# LazeMEGA.net
KiCad netlist of a schematic drawn in Altium Designer
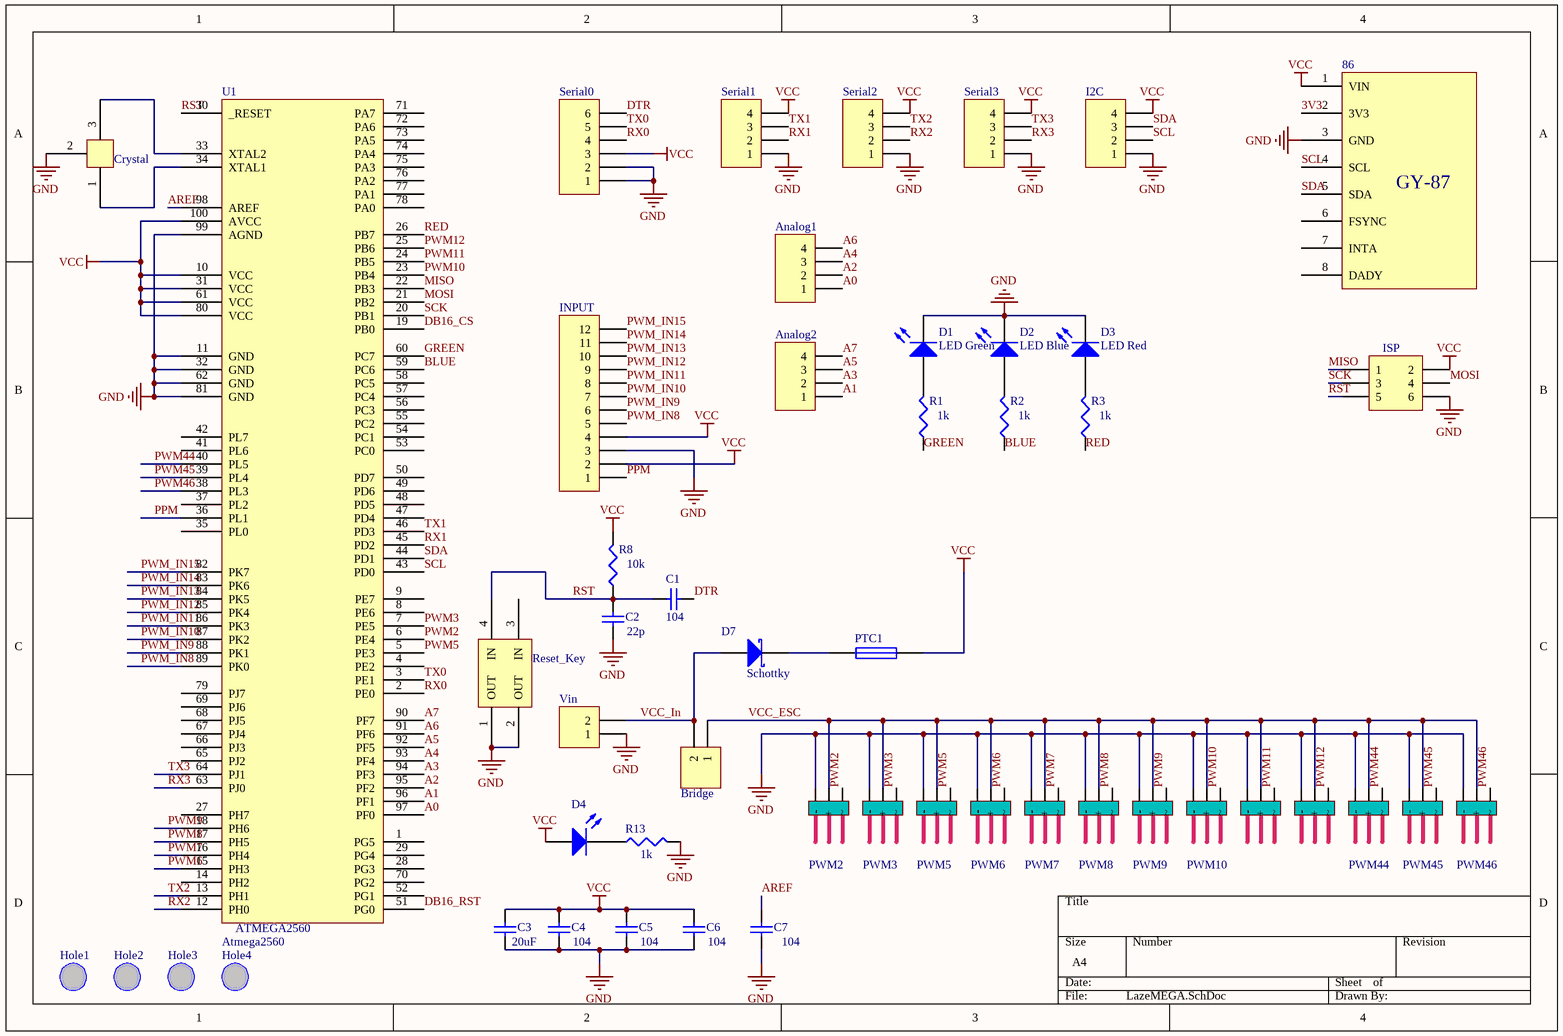
[diagram p0: LazeMEGA.SchDoc]

(export (version "E")
  (design (tool "Eeschema 10.0.6"))
  (components
    (comp (ref "86") (value "~") (footprint "GY-87") (libsource (lib "Drone") (part "GY-87")))
    (comp (ref "Analog1")
      (value "Header 4")
      (footprint "HDR1X4")
      (description "Header, 4-Pin")
      (fields (field (name "PUBLISHER") "Altium Limited"))
      (libsource (lib "Miscellaneous Connectors") (part "Header 4"))
    )
    (comp (ref "Analog2")
      (value "Header 4")
      (footprint "HDR1X4")
      (description "Header, 4-Pin")
      (fields (field (name "PUBLISHER") "Altium Limited"))
      (libsource (lib "Miscellaneous Connectors") (part "Header 4"))
    )
    (comp (ref "Bridge")
      (value "Header 2")
      (footprint "HDR1X2")
      (description "Header, 2-Pin")
      (fields (field (name "PUBLISHER") "Altium Limited"))
      (libsource (lib "Miscellaneous Connectors") (part "Header 2"))
    )
    (comp (ref "C1")
      (value "104")
      (footprint "CAPC1608L")
      (description "Capacitor (Semiconductor SIM Model)")
      (fields (field (name "PUBLISHER") "Altium Limited"))
      (libsource (lib "Miscellaneous Devices") (part "Cap Semi"))
    )
    (comp (ref "C2")
      (value "22p")
      (footprint "CAPC1608L")
      (description "Capacitor (Semiconductor SIM Model)")
      (fields (field (name "PUBLISHER") "Altium Limited"))
      (libsource (lib "Miscellaneous Devices") (part "Cap Semi"))
    )
    (comp (ref "C3")
      (value "20uF")
      (footprint "CAPC3216L")
      (description "Capacitor (Semiconductor SIM Model)")
      (fields (field (name "PUBLISHER") "Altium Limited"))
      (libsource (lib "Miscellaneous Devices") (part "Cap Semi"))
    )
    (comp (ref "C4")
      (value "104")
      (footprint "CAPC1608L")
      (description "Capacitor (Semiconductor SIM Model)")
      (fields (field (name "PUBLISHER") "Altium Limited"))
      (libsource (lib "Miscellaneous Devices") (part "Cap Semi"))
    )
    (comp (ref "C5")
      (value "104")
      (footprint "CAPC1608L")
      (description "Capacitor (Semiconductor SIM Model)")
      (fields (field (name "PUBLISHER") "Altium Limited"))
      (libsource (lib "Miscellaneous Devices") (part "Cap Semi"))
    )
    (comp (ref "C6")
      (value "104")
      (footprint "CAPC1608L")
      (description "Capacitor (Semiconductor SIM Model)")
      (fields (field (name "PUBLISHER") "Altium Limited"))
      (libsource (lib "Miscellaneous Devices") (part "Cap Semi"))
    )
    (comp (ref "C7")
      (value "104")
      (footprint "CAPC1608L")
      (description "Capacitor (Semiconductor SIM Model)")
      (fields (field (name "PUBLISHER") "Altium Limited"))
      (libsource (lib "Miscellaneous Devices") (part "Cap Semi"))
    )
    (comp (ref "Crystal")
      (value "Crystal 16M")
      (footprint "Crystal3Foot")
      (libsource (lib "Drone") (part "Crystal3Foot"))
    )
    (comp (ref "D1")
      (value "LED Green")
      (footprint "CAPC2012L")
      (description "Typical RED, GREEN, YELLOW, AMBER GaAs LED")
      (fields (field (name "PUBLISHER") "Altium Limited"))
      (libsource (lib "Miscellaneous Devices") (part "LED2"))
    )
    (comp (ref "D2")
      (value "LED Blue")
      (footprint "CAPC2012L")
      (description "Typical RED, GREEN, YELLOW, AMBER GaAs LED")
      (fields (field (name "PUBLISHER") "Altium Limited"))
      (libsource (lib "Miscellaneous Devices") (part "LED2"))
    )
    (comp (ref "D3")
      (value "LED Red")
      (footprint "CAPC2012L")
      (description "Typical RED, GREEN, YELLOW, AMBER GaAs LED")
      (fields (field (name "PUBLISHER") "Altium Limited"))
      (libsource (lib "Miscellaneous Devices") (part "LED2"))
    )
    (comp (ref "D4")
      (value "LED Red")
      (footprint "CAPC2012L")
      (description "Typical RED, GREEN, YELLOW, AMBER GaAs LED")
      (fields (field (name "PUBLISHER") "Altium Limited"))
      (libsource (lib "Miscellaneous Devices") (part "LED2"))
    )
    (comp (ref "D7")
      (value "Schottky")
      (footprint "CAPC3216L")
      (description "Schottky Diode")
      (fields (field (name "PUBLISHER") "Altium Limited"))
      (libsource (lib "Miscellaneous Devices") (part "D Schottky"))
    )
    (comp (ref "Hole1")
      (value "3mmHole")
      (footprint "3mmHoleSmall")
      (libsource (lib "Drone") (part "3mmHole"))
    )
    (comp (ref "Hole2")
      (value "3mmHole")
      (footprint "3mmHoleSmall")
      (libsource (lib "Drone") (part "3mmHole"))
    )
    (comp (ref "Hole3")
      (value "3mmHole")
      (footprint "3mmHoleSmall")
      (libsource (lib "Drone") (part "3mmHole"))
    )
    (comp (ref "Hole4")
      (value "3mmHole")
      (footprint "3mmHoleSmall")
      (libsource (lib "Drone") (part "3mmHole"))
    )
    (comp (ref "I2C")
      (value "Header 4")
      (footprint "HDR1X4")
      (description "Header, 4-Pin")
      (fields (field (name "PUBLISHER") "Altium Limited"))
      (libsource (lib "Miscellaneous Connectors") (part "Header 4"))
    )
    (comp (ref "INPUT")
      (value "Header 12")
      (footprint "HDR1X12")
      (description "Header, 12-Pin")
      (fields (field (name "PUBLISHER") "Altium Limited"))
      (libsource (lib "Miscellaneous Connectors") (part "Header 12"))
    )
    (comp (ref "ISP")
      (value "Header 3X2")
      (footprint "HDR2X3")
      (description "Header, 3-Pin, Dual row")
      (fields (field (name "PUBLISHER") "Altium Limited"))
      (libsource (lib "Miscellaneous Connectors") (part "Header 3X2"))
    )
    (comp (ref "JP1")
      (value "Servo out 1")
      (footprint "JP")
      (description "Header, 3-Pin, 0.1\"")
      (fields (field (name "MANUFACTURER") "Generic Components"))
      (libsource (lib "Drone") (part "Hdr 3 Pin 0.1"))
    )
    (comp (ref "JP2")
      (value "Servo out 1")
      (footprint "JP")
      (description "Header, 3-Pin, 0.1\"")
      (fields (field (name "MANUFACTURER") "Generic Components"))
      (libsource (lib "Drone") (part "Hdr 3 Pin 0.1"))
    )
    (comp (ref "PTC1")
      (value "Fuse")
      (footprint "CAPC3216L")
      (fields (field (name "PUBLISHER") "Altium Limited"))
      (libsource (lib "Miscellaneous Devices") (part "Fuse 1"))
    )
    (comp (ref "PWM2")
      (value "Servo out 1")
      (footprint "JP")
      (description "Header, 3-Pin, 0.1\"")
      (fields (field (name "MANUFACTURER") "Generic Components"))
      (libsource (lib "Drone") (part "Hdr 3 Pin 0.1"))
    )
    (comp (ref "PWM3")
      (value "Servo out 1")
      (footprint "JP")
      (description "Header, 3-Pin, 0.1\"")
      (fields (field (name "MANUFACTURER") "Generic Components"))
      (libsource (lib "Drone") (part "Hdr 3 Pin 0.1"))
    )
    (comp (ref "PWM5")
      (value "Servo out 1")
      (footprint "JP")
      (description "Header, 3-Pin, 0.1\"")
      (fields (field (name "MANUFACTURER") "Generic Components"))
      (libsource (lib "Drone") (part "Hdr 3 Pin 0.1"))
    )
    (comp (ref "PWM6")
      (value "Servo out 1")
      (footprint "JP")
      (description "Header, 3-Pin, 0.1\"")
      (fields (field (name "MANUFACTURER") "Generic Components"))
      (libsource (lib "Drone") (part "Hdr 3 Pin 0.1"))
    )
    (comp (ref "PWM7")
      (value "Servo out 1")
      (footprint "JP")
      (description "Header, 3-Pin, 0.1\"")
      (fields (field (name "MANUFACTURER") "Generic Components"))
      (libsource (lib "Drone") (part "Hdr 3 Pin 0.1"))
    )
    (comp (ref "PWM8")
      (value "Servo out 1")
      (footprint "JP")
      (description "Header, 3-Pin, 0.1\"")
      (fields (field (name "MANUFACTURER") "Generic Components"))
      (libsource (lib "Drone") (part "Hdr 3 Pin 0.1"))
    )
    (comp (ref "PWM9")
      (value "Servo out 1")
      (footprint "JP")
      (description "Header, 3-Pin, 0.1\"")
      (fields (field (name "MANUFACTURER") "Generic Components"))
      (libsource (lib "Drone") (part "Hdr 3 Pin 0.1"))
    )
    (comp (ref "PWM10")
      (value "Servo out 1")
      (footprint "JP")
      (description "Header, 3-Pin, 0.1\"")
      (fields (field (name "MANUFACTURER") "Generic Components"))
      (libsource (lib "Drone") (part "Hdr 3 Pin 0.1"))
    )
    (comp (ref "PWM44")
      (value "Servo out 1")
      (footprint "JP")
      (description "Header, 3-Pin, 0.1\"")
      (fields (field (name "MANUFACTURER") "Generic Components"))
      (libsource (lib "Drone") (part "Hdr 3 Pin 0.1"))
    )
    (comp (ref "PWM45")
      (value "Servo out 1")
      (footprint "JP")
      (description "Header, 3-Pin, 0.1\"")
      (fields (field (name "MANUFACTURER") "Generic Components"))
      (libsource (lib "Drone") (part "Hdr 3 Pin 0.1"))
    )
    (comp (ref "PWM46")
      (value "Servo out 1")
      (footprint "JP")
      (description "Header, 3-Pin, 0.1\"")
      (fields (field (name "MANUFACTURER") "Generic Components"))
      (libsource (lib "Drone") (part "Hdr 3 Pin 0.1"))
    )
    (comp (ref "R1")
      (value "1k")
      (footprint "RESC1608L")
      (description "Resistor")
      (fields (field (name "PUBLISHER") "Altium Limited"))
      (libsource (lib "Miscellaneous Devices") (part "Res3"))
    )
    (comp (ref "R2")
      (value "1k")
      (footprint "RESC1608L")
      (description "Resistor")
      (fields (field (name "PUBLISHER") "Altium Limited"))
      (libsource (lib "Miscellaneous Devices") (part "Res3"))
    )
    (comp (ref "R3")
      (value "1k")
      (footprint "RESC1608L")
      (description "Resistor")
      (fields (field (name "PUBLISHER") "Altium Limited"))
      (libsource (lib "Miscellaneous Devices") (part "Res3"))
    )
    (comp (ref "R8")
      (value "10k")
      (footprint "RESC1608L")
      (description "Resistor")
      (fields (field (name "PUBLISHER") "Altium Limited"))
      (libsource (lib "Miscellaneous Devices") (part "Res3"))
    )
    (comp (ref "R13")
      (value "1k")
      (footprint "RESC1608L")
      (description "Resistor")
      (fields (field (name "PUBLISHER") "Altium Limited"))
      (libsource (lib "Miscellaneous Devices") (part "Res3"))
    )
    (comp (ref "Reset_Key") (value "Key") (footprint "Key") (libsource (lib "Drone") (part "Key")))
    (comp (ref "Serial0")
      (value "Header 6")
      (footprint "HDR1X6")
      (description "Header, 6-Pin")
      (fields (field (name "PUBLISHER") "Altium Limited"))
      (libsource (lib "Miscellaneous Connectors") (part "Header 6"))
    )
    (comp (ref "Serial1")
      (value "Header 4")
      (footprint "HDR1X4")
      (description "Header, 4-Pin")
      (fields (field (name "PUBLISHER") "Altium Limited"))
      (libsource (lib "Miscellaneous Connectors") (part "Header 4"))
    )
    (comp (ref "Serial2")
      (value "Header 4")
      (footprint "HDR1X4")
      (description "Header, 4-Pin")
      (fields (field (name "PUBLISHER") "Altium Limited"))
      (libsource (lib "Miscellaneous Connectors") (part "Header 4"))
    )
    (comp (ref "Serial3")
      (value "Header 4")
      (footprint "HDR1X4")
      (description "Header, 4-Pin")
      (fields (field (name "PUBLISHER") "Altium Limited"))
      (libsource (lib "Miscellaneous Connectors") (part "Header 4"))
    )
    (comp (ref "U1")
      (value "Atmega2560")
      (footprint "ATMEGA2560")
      (libsource (lib "Drone") (part "Atmega2560"))
    )
    (comp (ref "Vin")
      (value "Header 2")
      (footprint "HDR1X2")
      (description "Header, 2-Pin")
      (fields (field (name "PUBLISHER") "Altium Limited"))
      (libsource (lib "") (part "Header 2_1"))
    )
  )
  (nets
    (net (code "1") (name "/3V3") (class "Default")
      (node (ref "86") (pin "2") (pinfunction "3V3_2") (pintype "passive"))
    )
    (net (code "2") (name "/A0") (class "Default")
      (node (ref "Analog1") (pin "1") (pinfunction "1_1") (pintype "passive"))
      (node (ref "U1") (pin "97") (pinfunction "PF0_97") (pintype "passive"))
    )
    (net (code "3") (name "/A1") (class "Default")
      (node (ref "Analog2") (pin "1") (pinfunction "1_1") (pintype "passive"))
      (node (ref "U1") (pin "96") (pinfunction "PF1_96") (pintype "passive"))
    )
    (net (code "4") (name "/A2") (class "Default")
      (node (ref "Analog1") (pin "2") (pinfunction "2_2") (pintype "passive"))
      (node (ref "U1") (pin "95") (pinfunction "PF2_95") (pintype "passive"))
    )
    (net (code "5") (name "/A3") (class "Default")
      (node (ref "Analog2") (pin "2") (pinfunction "2_2") (pintype "passive"))
      (node (ref "U1") (pin "94") (pinfunction "PF3_94") (pintype "passive"))
    )
    (net (code "6") (name "/A4") (class "Default")
      (node (ref "Analog1") (pin "3") (pinfunction "3_3") (pintype "passive"))
      (node (ref "U1") (pin "93") (pinfunction "PF4_93") (pintype "passive"))
    )
    (net (code "7") (name "/A5") (class "Default")
      (node (ref "Analog2") (pin "3") (pinfunction "3_3") (pintype "passive"))
      (node (ref "U1") (pin "92") (pinfunction "PF5_92") (pintype "passive"))
    )
    (net (code "8") (name "/A6") (class "Default")
      (node (ref "Analog1") (pin "4") (pinfunction "4_4") (pintype "passive"))
      (node (ref "U1") (pin "91") (pinfunction "PF6_91") (pintype "passive"))
    )
    (net (code "9") (name "/A7") (class "Default")
      (node (ref "Analog2") (pin "4") (pinfunction "4_4") (pintype "passive"))
      (node (ref "U1") (pin "90") (pinfunction "PF7_90") (pintype "passive"))
    )
    (net (code "10") (name "/AREF") (class "Default")
      (node (ref "C7") (pin "2") (pinfunction "2_2") (pintype "passive"))
      (node (ref "U1") (pin "98") (pinfunction "AREF_98") (pintype "passive"))
    )
    (net (code "11") (name "/BLUE") (class "Default")
      (node (ref "R2") (pin "1") (pinfunction "1_1") (pintype "passive"))
      (node (ref "U1") (pin "59") (pinfunction "PC6_59") (pintype "passive"))
    )
    (net (code "12") (name "/DB16_CS") (class "Default")
      (node (ref "U1") (pin "19") (pinfunction "PB0_19") (pintype "passive"))
    )
    (net (code "13") (name "/DB16_RST") (class "Default")
      (node (ref "U1") (pin "51") (pinfunction "PG0_51") (pintype "passive"))
    )
    (net (code "14") (name "/DTR") (class "Default")
      (node (ref "C1") (pin "2") (pinfunction "2_2") (pintype "passive"))
      (node (ref "Serial0") (pin "6") (pinfunction "6_6") (pintype "passive"))
    )
    (net (code "15") (name "/GREEN") (class "Default")
      (node (ref "R1") (pin "1") (pinfunction "1_1") (pintype "passive"))
      (node (ref "U1") (pin "60") (pinfunction "PC7_60") (pintype "passive"))
    )
    (net (code "16") (name "/MISO") (class "Default")
      (node (ref "ISP") (pin "1") (pinfunction "1_1") (pintype "passive"))
      (node (ref "U1") (pin "22") (pinfunction "PB3_22") (pintype "passive"))
    )
    (net (code "17") (name "/MOSI") (class "Default")
      (node (ref "ISP") (pin "4") (pinfunction "4_4") (pintype "passive"))
      (node (ref "U1") (pin "21") (pinfunction "PB2_21") (pintype "passive"))
    )
    (net (code "18") (name "/PPM") (class "Default")
      (node (ref "INPUT") (pin "1") (pinfunction "1_1") (pintype "passive"))
      (node (ref "U1") (pin "36") (pinfunction "PL1_36") (pintype "passive"))
    )
    (net (code "19") (name "/PWM2") (class "Default")
      (node (ref "PWM2") (pin "1") (pinfunction "~_1") (pintype "passive"))
      (node (ref "U1") (pin "6") (pinfunction "PE4_6") (pintype "passive"))
    )
    (net (code "20") (name "/PWM3") (class "Default")
      (node (ref "PWM3") (pin "1") (pinfunction "~_1") (pintype "passive"))
      (node (ref "U1") (pin "7") (pinfunction "PE5_7") (pintype "passive"))
    )
    (net (code "21") (name "/PWM5") (class "Default")
      (node (ref "PWM5") (pin "1") (pinfunction "~_1") (pintype "passive"))
      (node (ref "U1") (pin "5") (pinfunction "PE3_5") (pintype "passive"))
    )
    (net (code "22") (name "/PWM6") (class "Default")
      (node (ref "PWM6") (pin "1") (pinfunction "~_1") (pintype "passive"))
      (node (ref "U1") (pin "15") (pinfunction "PH3_15") (pintype "passive"))
    )
    (net (code "23") (name "/PWM7") (class "Default")
      (node (ref "PWM7") (pin "1") (pinfunction "~_1") (pintype "passive"))
      (node (ref "U1") (pin "16") (pinfunction "PH4_16") (pintype "passive"))
    )
    (net (code "24") (name "/PWM8") (class "Default")
      (node (ref "PWM8") (pin "1") (pinfunction "~_1") (pintype "passive"))
      (node (ref "U1") (pin "17") (pinfunction "PH5_17") (pintype "passive"))
    )
    (net (code "25") (name "/PWM9") (class "Default")
      (node (ref "PWM9") (pin "1") (pinfunction "~_1") (pintype "passive"))
      (node (ref "U1") (pin "18") (pinfunction "PH6_18") (pintype "passive"))
    )
    (net (code "26") (name "/PWM10") (class "Default")
      (node (ref "PWM10") (pin "1") (pinfunction "~_1") (pintype "passive"))
      (node (ref "U1") (pin "23") (pinfunction "PB4_23") (pintype "passive"))
    )
    (net (code "27") (name "/PWM11") (class "Default")
      (node (ref "JP1") (pin "1") (pinfunction "~_1") (pintype "passive"))
      (node (ref "U1") (pin "24") (pinfunction "PB5_24") (pintype "passive"))
    )
    (net (code "28") (name "/PWM12") (class "Default")
      (node (ref "JP2") (pin "1") (pinfunction "~_1") (pintype "passive"))
      (node (ref "U1") (pin "25") (pinfunction "PB6_25") (pintype "passive"))
    )
    (net (code "29") (name "/PWM44") (class "Default")
      (node (ref "PWM44") (pin "1") (pinfunction "~_1") (pintype "passive"))
      (node (ref "U1") (pin "40") (pinfunction "PL5_40") (pintype "passive"))
    )
    (net (code "30") (name "/PWM45") (class "Default")
      (node (ref "PWM45") (pin "1") (pinfunction "~_1") (pintype "passive"))
      (node (ref "U1") (pin "39") (pinfunction "PL4_39") (pintype "passive"))
    )
    (net (code "31") (name "/PWM46") (class "Default")
      (node (ref "PWM46") (pin "1") (pinfunction "~_1") (pintype "passive"))
      (node (ref "U1") (pin "38") (pinfunction "PL3_38") (pintype "passive"))
    )
    (net (code "32") (name "/PWM_IN8") (class "Default")
      (node (ref "INPUT") (pin "5") (pinfunction "5_5") (pintype "passive"))
      (node (ref "U1") (pin "89") (pinfunction "PK0_89") (pintype "passive"))
    )
    (net (code "33") (name "/PWM_IN9") (class "Default")
      (node (ref "INPUT") (pin "6") (pinfunction "6_6") (pintype "passive"))
      (node (ref "U1") (pin "88") (pinfunction "PK1_88") (pintype "passive"))
    )
    (net (code "34") (name "/PWM_IN10") (class "Default")
      (node (ref "INPUT") (pin "7") (pinfunction "7_7") (pintype "passive"))
      (node (ref "U1") (pin "87") (pinfunction "PK2_87") (pintype "passive"))
    )
    (net (code "35") (name "/PWM_IN11") (class "Default")
      (node (ref "INPUT") (pin "8") (pinfunction "8_8") (pintype "passive"))
      (node (ref "U1") (pin "86") (pinfunction "PK3_86") (pintype "passive"))
    )
    (net (code "36") (name "/PWM_IN12") (class "Default")
      (node (ref "INPUT") (pin "9") (pinfunction "9_9") (pintype "passive"))
      (node (ref "U1") (pin "85") (pinfunction "PK4_85") (pintype "passive"))
    )
    (net (code "37") (name "/PWM_IN13") (class "Default")
      (node (ref "INPUT") (pin "10") (pinfunction "10_10") (pintype "passive"))
      (node (ref "U1") (pin "84") (pinfunction "PK5_84") (pintype "passive"))
    )
    (net (code "38") (name "/PWM_IN14") (class "Default")
      (node (ref "INPUT") (pin "11") (pinfunction "11_11") (pintype "passive"))
      (node (ref "U1") (pin "83") (pinfunction "PK6_83") (pintype "passive"))
    )
    (net (code "39") (name "/PWM_IN15") (class "Default")
      (node (ref "INPUT") (pin "12") (pinfunction "12_12") (pintype "passive"))
      (node (ref "U1") (pin "82") (pinfunction "PK7_82") (pintype "passive"))
    )
    (net (code "40") (name "/RED") (class "Default")
      (node (ref "R3") (pin "1") (pinfunction "1_1") (pintype "passive"))
      (node (ref "U1") (pin "26") (pinfunction "PB7_26") (pintype "passive"))
    )
    (net (code "41") (name "/RST") (class "Default")
      (node (ref "C1") (pin "1") (pinfunction "1_1") (pintype "passive"))
      (node (ref "C2") (pin "1") (pinfunction "1_1") (pintype "passive"))
      (node (ref "ISP") (pin "5") (pinfunction "5_5") (pintype "passive"))
      (node (ref "R8") (pin "1") (pinfunction "1_1") (pintype "passive"))
      (node (ref "Reset_Key") (pin "4") (pinfunction "IN_4") (pintype "passive"))
      (node (ref "U1") (pin "30") (pinfunction "_RESET_30") (pintype "passive"))
    )
    (net (code "42") (name "/RX0") (class "Default")
      (node (ref "Serial0") (pin "4") (pinfunction "4_4") (pintype "passive"))
      (node (ref "U1") (pin "2") (pinfunction "PE0_2") (pintype "passive"))
    )
    (net (code "43") (name "/RX1") (class "Default")
      (node (ref "Serial1") (pin "2") (pinfunction "2_2") (pintype "passive"))
      (node (ref "U1") (pin "45") (pinfunction "PD2_45") (pintype "passive"))
    )
    (net (code "44") (name "/RX2") (class "Default")
      (node (ref "Serial2") (pin "2") (pinfunction "2_2") (pintype "passive"))
      (node (ref "U1") (pin "12") (pinfunction "PH0_12") (pintype "passive"))
    )
    (net (code "45") (name "/RX3") (class "Default")
      (node (ref "Serial3") (pin "2") (pinfunction "2_2") (pintype "passive"))
      (node (ref "U1") (pin "63") (pinfunction "PJ0_63") (pintype "passive"))
    )
    (net (code "46") (name "/SCK") (class "Default")
      (node (ref "ISP") (pin "3") (pinfunction "3_3") (pintype "passive"))
      (node (ref "U1") (pin "20") (pinfunction "PB1_20") (pintype "passive"))
    )
    (net (code "47") (name "/SCL") (class "Default")
      (node (ref "86") (pin "4") (pinfunction "SCL_4") (pintype "passive"))
      (node (ref "I2C") (pin "2") (pinfunction "2_2") (pintype "passive"))
      (node (ref "U1") (pin "43") (pinfunction "PD0_43") (pintype "passive"))
    )
    (net (code "48") (name "/SDA") (class "Default")
      (node (ref "86") (pin "5") (pinfunction "SDA_5") (pintype "passive"))
      (node (ref "I2C") (pin "3") (pinfunction "3_3") (pintype "passive"))
      (node (ref "U1") (pin "44") (pinfunction "PD1_44") (pintype "passive"))
    )
    (net (code "49") (name "/TX0") (class "Default")
      (node (ref "Serial0") (pin "5") (pinfunction "5_5") (pintype "passive"))
      (node (ref "U1") (pin "3") (pinfunction "PE1_3") (pintype "passive"))
    )
    (net (code "50") (name "/TX1") (class "Default")
      (node (ref "Serial1") (pin "3") (pinfunction "3_3") (pintype "passive"))
      (node (ref "U1") (pin "46") (pinfunction "PD3_46") (pintype "passive"))
    )
    (net (code "51") (name "/TX2") (class "Default")
      (node (ref "Serial2") (pin "3") (pinfunction "3_3") (pintype "passive"))
      (node (ref "U1") (pin "13") (pinfunction "PH1_13") (pintype "passive"))
    )
    (net (code "52") (name "/TX3") (class "Default")
      (node (ref "Serial3") (pin "3") (pinfunction "3_3") (pintype "passive"))
      (node (ref "U1") (pin "64") (pinfunction "PJ1_64") (pintype "passive"))
    )
    (net (code "53") (name "/VCC_ESC") (class "Default")
      (node (ref "Bridge") (pin "1") (pinfunction "1_1") (pintype "passive"))
      (node (ref "JP1") (pin "2") (pinfunction "+_2") (pintype "passive"))
      (node (ref "JP2") (pin "2") (pinfunction "+_2") (pintype "passive"))
      (node (ref "PWM10") (pin "2") (pinfunction "+_2") (pintype "passive"))
      (node (ref "PWM2") (pin "2") (pinfunction "+_2") (pintype "passive"))
      (node (ref "PWM3") (pin "2") (pinfunction "+_2") (pintype "passive"))
      (node (ref "PWM44") (pin "2") (pinfunction "+_2") (pintype "passive"))
      (node (ref "PWM45") (pin "2") (pinfunction "+_2") (pintype "passive"))
      (node (ref "PWM46") (pin "2") (pinfunction "+_2") (pintype "passive"))
      (node (ref "PWM5") (pin "2") (pinfunction "+_2") (pintype "passive"))
      (node (ref "PWM6") (pin "2") (pinfunction "+_2") (pintype "passive"))
      (node (ref "PWM7") (pin "2") (pinfunction "+_2") (pintype "passive"))
      (node (ref "PWM8") (pin "2") (pinfunction "+_2") (pintype "passive"))
      (node (ref "PWM9") (pin "2") (pinfunction "+_2") (pintype "passive"))
    )
    (net (code "54") (name "/VCC_In") (class "Default")
      (node (ref "Bridge") (pin "2") (pinfunction "2_2") (pintype "passive"))
      (node (ref "D7") (pin "1") (pinfunction "A_1") (pintype "passive"))
      (node (ref "Vin") (pin "2") (pinfunction "2_2") (pintype "passive"))
    )
    (net (code "55") (name "GND") (class "Default")
      (node (ref "86") (pin "3") (pinfunction "GND_3") (pintype "passive"))
      (node (ref "C2") (pin "2") (pinfunction "2_2") (pintype "passive"))
      (node (ref "C3") (pin "1") (pinfunction "1_1") (pintype "passive"))
      (node (ref "C4") (pin "1") (pinfunction "1_1") (pintype "passive"))
      (node (ref "C5") (pin "1") (pinfunction "1_1") (pintype "passive"))
      (node (ref "C6") (pin "1") (pinfunction "1_1") (pintype "passive"))
      (node (ref "C7") (pin "1") (pinfunction "1_1") (pintype "passive"))
      (node (ref "Crystal") (pin "2") (pinfunction "2_2") (pintype "passive"))
      (node (ref "D1") (pin "2") (pinfunction "K_2") (pintype "passive"))
      (node (ref "D2") (pin "2") (pinfunction "K_2") (pintype "passive"))
      (node (ref "D3") (pin "2") (pinfunction "K_2") (pintype "passive"))
      (node (ref "I2C") (pin "1") (pinfunction "1_1") (pintype "passive"))
      (node (ref "INPUT") (pin "3") (pinfunction "3_3") (pintype "passive"))
      (node (ref "ISP") (pin "6") (pinfunction "6_6") (pintype "passive"))
      (node (ref "JP1") (pin "3") (pinfunction "-_3") (pintype "passive"))
      (node (ref "JP2") (pin "3") (pinfunction "-_3") (pintype "passive"))
      (node (ref "PWM10") (pin "3") (pinfunction "-_3") (pintype "passive"))
      (node (ref "PWM2") (pin "3") (pinfunction "-_3") (pintype "passive"))
      (node (ref "PWM3") (pin "3") (pinfunction "-_3") (pintype "passive"))
      (node (ref "PWM44") (pin "3") (pinfunction "-_3") (pintype "passive"))
      (node (ref "PWM45") (pin "3") (pinfunction "-_3") (pintype "passive"))
      (node (ref "PWM46") (pin "3") (pinfunction "-_3") (pintype "passive"))
      (node (ref "PWM5") (pin "3") (pinfunction "-_3") (pintype "passive"))
      (node (ref "PWM6") (pin "3") (pinfunction "-_3") (pintype "passive"))
      (node (ref "PWM7") (pin "3") (pinfunction "-_3") (pintype "passive"))
      (node (ref "PWM8") (pin "3") (pinfunction "-_3") (pintype "passive"))
      (node (ref "PWM9") (pin "3") (pinfunction "-_3") (pintype "passive"))
      (node (ref "R13") (pin "2") (pinfunction "2_2") (pintype "passive"))
      (node (ref "Reset_Key") (pin "1") (pinfunction "OUT_1") (pintype "passive"))
      (node (ref "Reset_Key") (pin "2") (pinfunction "OUT_2") (pintype "passive"))
      (node (ref "Serial0") (pin "1") (pinfunction "1_1") (pintype "passive"))
      (node (ref "Serial0") (pin "2") (pinfunction "2_2") (pintype "passive"))
      (node (ref "Serial1") (pin "1") (pinfunction "1_1") (pintype "passive"))
      (node (ref "Serial2") (pin "1") (pinfunction "1_1") (pintype "passive"))
      (node (ref "Serial3") (pin "1") (pinfunction "1_1") (pintype "passive"))
      (node (ref "U1") (pin "11") (pinfunction "GND_11") (pintype "passive"))
      (node (ref "U1") (pin "32") (pinfunction "GND_32") (pintype "passive"))
      (node (ref "U1") (pin "62") (pinfunction "GND_62") (pintype "passive"))
      (node (ref "U1") (pin "81") (pinfunction "GND_81") (pintype "passive"))
      (node (ref "U1") (pin "99") (pinfunction "AGND_99") (pintype "passive"))
      (node (ref "Vin") (pin "1") (pinfunction "1_1") (pintype "passive"))
    )
    (net (code "56") (name "Net-(Crystal-0)") (class "Default")
      (node (ref "Crystal") (pin "1") (pinfunction "0_1") (pintype "passive"))
      (node (ref "U1") (pin "34") (pinfunction "XTAL1_34") (pintype "passive"))
    )
    (net (code "57") (name "Net-(Crystal-1)") (class "Default")
      (node (ref "Crystal") (pin "3") (pinfunction "1_3") (pintype "passive"))
      (node (ref "U1") (pin "33") (pinfunction "XTAL2_33") (pintype "passive"))
    )
    (net (code "58") (name "Net-(D1-A)") (class "Default")
      (node (ref "D1") (pin "1") (pinfunction "A_1") (pintype "passive"))
      (node (ref "R1") (pin "2") (pinfunction "2_2") (pintype "passive"))
    )
    (net (code "59") (name "Net-(D2-A)") (class "Default")
      (node (ref "D2") (pin "1") (pinfunction "A_1") (pintype "passive"))
      (node (ref "R2") (pin "2") (pinfunction "2_2") (pintype "passive"))
    )
    (net (code "60") (name "Net-(D3-A)") (class "Default")
      (node (ref "D3") (pin "1") (pinfunction "A_1") (pintype "passive"))
      (node (ref "R3") (pin "2") (pinfunction "2_2") (pintype "passive"))
    )
    (net (code "61") (name "Net-(D4-K)") (class "Default")
      (node (ref "D4") (pin "2") (pinfunction "K_2") (pintype "passive"))
      (node (ref "R13") (pin "1") (pinfunction "1_1") (pintype "passive"))
    )
    (net (code "62") (name "Net-(D7-K)") (class "Default")
      (node (ref "D7") (pin "2") (pinfunction "K_2") (pintype "passive"))
      (node (ref "PTC1") (pin "1") (pinfunction "1_1") (pintype "passive"))
    )
    (net (code "63") (name "VCC") (class "Default")
      (node (ref "86") (pin "1") (pinfunction "VIN_1") (pintype "passive"))
      (node (ref "C3") (pin "2") (pinfunction "2_2") (pintype "passive"))
      (node (ref "C4") (pin "2") (pinfunction "2_2") (pintype "passive"))
      (node (ref "C5") (pin "2") (pinfunction "2_2") (pintype "passive"))
      (node (ref "C6") (pin "2") (pinfunction "2_2") (pintype "passive"))
      (node (ref "D4") (pin "1") (pinfunction "A_1") (pintype "passive"))
      (node (ref "I2C") (pin "4") (pinfunction "4_4") (pintype "passive"))
      (node (ref "INPUT") (pin "2") (pinfunction "2_2") (pintype "passive"))
      (node (ref "INPUT") (pin "4") (pinfunction "4_4") (pintype "passive"))
      (node (ref "ISP") (pin "2") (pinfunction "2_2") (pintype "passive"))
      (node (ref "PTC1") (pin "2") (pinfunction "2_2") (pintype "passive"))
      (node (ref "R8") (pin "2") (pinfunction "2_2") (pintype "passive"))
      (node (ref "Serial0") (pin "3") (pinfunction "3_3") (pintype "passive"))
      (node (ref "Serial1") (pin "4") (pinfunction "4_4") (pintype "passive"))
      (node (ref "Serial2") (pin "4") (pinfunction "4_4") (pintype "passive"))
      (node (ref "Serial3") (pin "4") (pinfunction "4_4") (pintype "passive"))
      (node (ref "U1") (pin "10") (pinfunction "VCC_10") (pintype "passive"))
      (node (ref "U1") (pin "100") (pinfunction "AVCC_100") (pintype "passive"))
      (node (ref "U1") (pin "31") (pinfunction "VCC_31") (pintype "passive"))
      (node (ref "U1") (pin "61") (pinfunction "VCC_61") (pintype "passive"))
      (node (ref "U1") (pin "80") (pinfunction "VCC_80") (pintype "passive"))
    )
    (net (code "64") (name "unconnected-(86-DADY-Pad8)") (class "Default")
      (node (ref "86") (pin "8") (pinfunction "DADY_8") (pintype "passive"))
    )
    (net (code "65") (name "unconnected-(86-FSYNC-Pad6)") (class "Default")
      (node (ref "86") (pin "6") (pinfunction "FSYNC_6") (pintype "passive"))
    )
    (net (code "66") (name "unconnected-(86-INTA-Pad7)") (class "Default")
      (node (ref "86") (pin "7") (pinfunction "INTA_7") (pintype "passive"))
    )
    (net (code "67") (name "unconnected-(Reset_Key-IN-Pad3)") (class "Default")
      (node (ref "Reset_Key") (pin "3") (pinfunction "IN_3") (pintype "passive"))
    )
    (net (code "68") (name "unconnected-(U1-PA0-Pad78)") (class "Default")
      (node (ref "U1") (pin "78") (pinfunction "PA0_78") (pintype "passive"))
    )
    (net (code "69") (name "unconnected-(U1-PA1-Pad77)") (class "Default")
      (node (ref "U1") (pin "77") (pinfunction "PA1_77") (pintype "passive"))
    )
    (net (code "70") (name "unconnected-(U1-PA2-Pad76)") (class "Default")
      (node (ref "U1") (pin "76") (pinfunction "PA2_76") (pintype "passive"))
    )
    (net (code "71") (name "unconnected-(U1-PA3-Pad75)") (class "Default")
      (node (ref "U1") (pin "75") (pinfunction "PA3_75") (pintype "passive"))
    )
    (net (code "72") (name "unconnected-(U1-PA4-Pad74)") (class "Default")
      (node (ref "U1") (pin "74") (pinfunction "PA4_74") (pintype "passive"))
    )
    (net (code "73") (name "unconnected-(U1-PA5-Pad73)") (class "Default")
      (node (ref "U1") (pin "73") (pinfunction "PA5_73") (pintype "passive"))
    )
    (net (code "74") (name "unconnected-(U1-PA6-Pad72)") (class "Default")
      (node (ref "U1") (pin "72") (pinfunction "PA6_72") (pintype "passive"))
    )
    (net (code "75") (name "unconnected-(U1-PA7-Pad71)") (class "Default")
      (node (ref "U1") (pin "71") (pinfunction "PA7_71") (pintype "passive"))
    )
    (net (code "76") (name "unconnected-(U1-PC0-Pad53)") (class "Default")
      (node (ref "U1") (pin "53") (pinfunction "PC0_53") (pintype "passive"))
    )
    (net (code "77") (name "unconnected-(U1-PC1-Pad54)") (class "Default")
      (node (ref "U1") (pin "54") (pinfunction "PC1_54") (pintype "passive"))
    )
    (net (code "78") (name "unconnected-(U1-PC2-Pad55)") (class "Default")
      (node (ref "U1") (pin "55") (pinfunction "PC2_55") (pintype "passive"))
    )
    (net (code "79") (name "unconnected-(U1-PC3-Pad56)") (class "Default")
      (node (ref "U1") (pin "56") (pinfunction "PC3_56") (pintype "passive"))
    )
    (net (code "80") (name "unconnected-(U1-PC4-Pad57)") (class "Default")
      (node (ref "U1") (pin "57") (pinfunction "PC4_57") (pintype "passive"))
    )
    (net (code "81") (name "unconnected-(U1-PC5-Pad58)") (class "Default")
      (node (ref "U1") (pin "58") (pinfunction "PC5_58") (pintype "passive"))
    )
    (net (code "82") (name "unconnected-(U1-PD4-Pad47)") (class "Default")
      (node (ref "U1") (pin "47") (pinfunction "PD4_47") (pintype "passive"))
    )
    (net (code "83") (name "unconnected-(U1-PD5-Pad48)") (class "Default")
      (node (ref "U1") (pin "48") (pinfunction "PD5_48") (pintype "passive"))
    )
    (net (code "84") (name "unconnected-(U1-PD6-Pad49)") (class "Default")
      (node (ref "U1") (pin "49") (pinfunction "PD6_49") (pintype "passive"))
    )
    (net (code "85") (name "unconnected-(U1-PD7-Pad50)") (class "Default")
      (node (ref "U1") (pin "50") (pinfunction "PD7_50") (pintype "passive"))
    )
    (net (code "86") (name "unconnected-(U1-PE2-Pad4)") (class "Default")
      (node (ref "U1") (pin "4") (pinfunction "PE2_4") (pintype "passive"))
    )
    (net (code "87") (name "unconnected-(U1-PE6-Pad8)") (class "Default")
      (node (ref "U1") (pin "8") (pinfunction "PE6_8") (pintype "passive"))
    )
    (net (code "88") (name "unconnected-(U1-PE7-Pad9)") (class "Default")
      (node (ref "U1") (pin "9") (pinfunction "PE7_9") (pintype "passive"))
    )
    (net (code "89") (name "unconnected-(U1-PG1-Pad52)") (class "Default")
      (node (ref "U1") (pin "52") (pinfunction "PG1_52") (pintype "passive"))
    )
    (net (code "90") (name "unconnected-(U1-PG2-Pad70)") (class "Default")
      (node (ref "U1") (pin "70") (pinfunction "PG2_70") (pintype "passive"))
    )
    (net (code "91") (name "unconnected-(U1-PG3-Pad28)") (class "Default")
      (node (ref "U1") (pin "28") (pinfunction "PG3_28") (pintype "passive"))
    )
    (net (code "92") (name "unconnected-(U1-PG4-Pad29)") (class "Default")
      (node (ref "U1") (pin "29") (pinfunction "PG4_29") (pintype "passive"))
    )
    (net (code "93") (name "unconnected-(U1-PG5-Pad1)") (class "Default")
      (node (ref "U1") (pin "1") (pinfunction "PG5_1") (pintype "passive"))
    )
    (net (code "94") (name "unconnected-(U1-PH2-Pad14)") (class "Default")
      (node (ref "U1") (pin "14") (pinfunction "PH2_14") (pintype "passive"))
    )
    (net (code "95") (name "unconnected-(U1-PH7-Pad27)") (class "Default")
      (node (ref "U1") (pin "27") (pinfunction "PH7_27") (pintype "passive"))
    )
    (net (code "96") (name "unconnected-(U1-PJ2-Pad65)") (class "Default")
      (node (ref "U1") (pin "65") (pinfunction "PJ2_65") (pintype "passive"))
    )
    (net (code "97") (name "unconnected-(U1-PJ3-Pad66)") (class "Default")
      (node (ref "U1") (pin "66") (pinfunction "PJ3_66") (pintype "passive"))
    )
    (net (code "98") (name "unconnected-(U1-PJ4-Pad67)") (class "Default")
      (node (ref "U1") (pin "67") (pinfunction "PJ4_67") (pintype "passive"))
    )
    (net (code "99") (name "unconnected-(U1-PJ5-Pad68)") (class "Default")
      (node (ref "U1") (pin "68") (pinfunction "PJ5_68") (pintype "passive"))
    )
    (net (code "100") (name "unconnected-(U1-PJ6-Pad69)") (class "Default")
      (node (ref "U1") (pin "69") (pinfunction "PJ6_69") (pintype "passive"))
    )
    (net (code "101") (name "unconnected-(U1-PJ7-Pad79)") (class "Default")
      (node (ref "U1") (pin "79") (pinfunction "PJ7_79") (pintype "passive"))
    )
    (net (code "102") (name "unconnected-(U1-PL0-Pad35)") (class "Default")
      (node (ref "U1") (pin "35") (pinfunction "PL0_35") (pintype "passive"))
    )
    (net (code "103") (name "unconnected-(U1-PL2-Pad37)") (class "Default")
      (node (ref "U1") (pin "37") (pinfunction "PL2_37") (pintype "passive"))
    )
    (net (code "104") (name "unconnected-(U1-PL6-Pad41)") (class "Default")
      (node (ref "U1") (pin "41") (pinfunction "PL6_41") (pintype "passive"))
    )
    (net (code "105") (name "unconnected-(U1-PL7-Pad42)") (class "Default")
      (node (ref "U1") (pin "42") (pinfunction "PL7_42") (pintype "passive"))
    )
  )
)
